# LED_driver_1_2.net
KiCad netlist of a schematic drawn in EAGLE
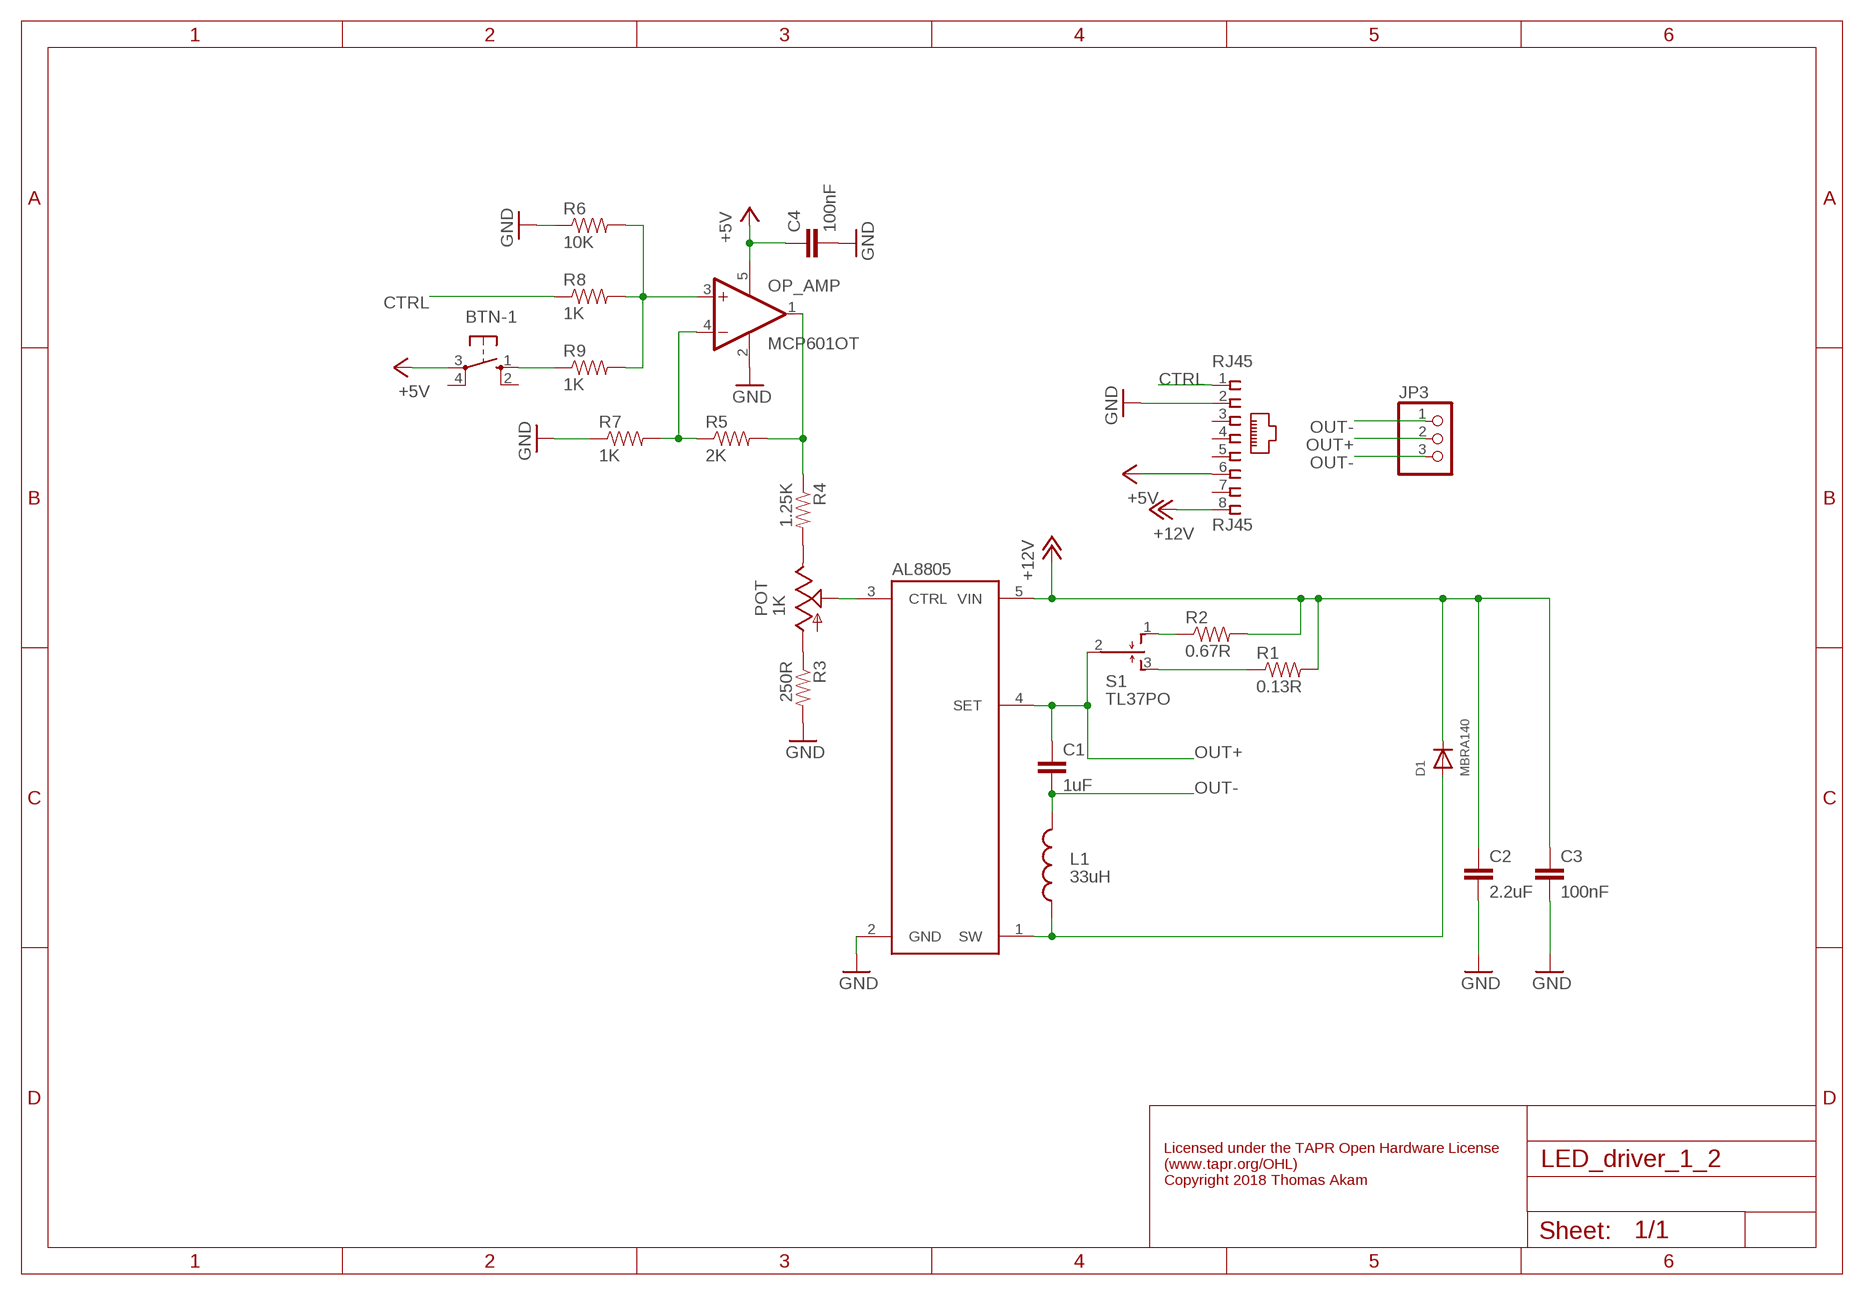
[diagram p0: schematic, sheet 1]

(export (version "E")
  (design (tool "Eeschema 10.0.6"))
  (components
    (comp (ref "AL8805")
      (value "AL8805")
      (footprint "eagle-import:SOT23-5")
      (libsource (lib "eagle-import") (part "AL8805"))
    )
    (comp (ref "BTN-1")
      (value "10-XX")
      (footprint "eagle-import:B3F-10XX")
      (fields (field (name "MPN") "B3F-1000"))
      (libsource (lib "eagle-import") (part "10-XX"))
    )
    (comp (ref "C1")
      (value "1uF")
      (footprint "eagle-import:C0805")
      (libsource (lib "eagle-import") (part "C-EUC0805"))
    )
    (comp (ref "C2")
      (value "2.2uF")
      (footprint "eagle-import:C0805")
      (libsource (lib "eagle-import") (part "C-EUC0805"))
    )
    (comp (ref "C3")
      (value "100nF")
      (footprint "eagle-import:C0805")
      (libsource (lib "eagle-import") (part "C-EUC0805"))
    )
    (comp (ref "C4")
      (value "100nF")
      (footprint "eagle-import:C0805")
      (libsource (lib "eagle-import") (part "C-EUC0805"))
    )
    (comp (ref "D1")
      (value "MBRA140")
      (footprint "eagle-import:SOD-123")
      (libsource (lib "eagle-import") (part "DIODESOD-123"))
    )
    (comp (ref "JP3")
      (value "PINHD-1X3")
      (footprint "eagle-import:1X03")
      (libsource (lib "eagle-import") (part "PINHD-1X3"))
    )
    (comp (ref "L1")
      (value "33uH")
      (footprint "eagle-import:SRN6045")
      (libsource (lib "eagle-import") (part "INDUCTORBOURNS_SRN6045"))
    )
    (comp (ref "OP_AMP")
      (value "MCP601OT")
      (footprint "eagle-import:SOT23-5")
      (libsource (lib "eagle-import") (part "MCP601OT"))
    )
    (comp (ref "POT")
      (value "1K")
      (footprint "eagle-import:RS3")
      (libsource (lib "eagle-import") (part "TRIM_US-RS3"))
    )
    (comp (ref "R1")
      (value "0.13R")
      (footprint "eagle-import:0805")
      (libsource (lib "eagle-import") (part "0.3OHM-1/8W-1%(0805)"))
    )
    (comp (ref "R2")
      (value "0.67R")
      (footprint "eagle-import:0805")
      (fields (field (name "PROD_ID") "RES-11622"))
      (libsource (lib "eagle-import") (part "0.3OHM-1/8W-1%(0805)"))
    )
    (comp (ref "R3")
      (value "250R")
      (footprint "eagle-import:0805")
      (fields (field (name "PROD_ID") "RES-11622"))
      (libsource (lib "eagle-import") (part "0.3OHM-1/8W-1%(0805)"))
    )
    (comp (ref "R4")
      (value "1.25K")
      (footprint "eagle-import:0805")
      (fields (field (name "PROD_ID") "RES-11622"))
      (libsource (lib "eagle-import") (part "0.3OHM-1/8W-1%(0805)"))
    )
    (comp (ref "R5")
      (value "2K")
      (footprint "eagle-import:0805")
      (fields (field (name "PROD_ID") "RES-11622"))
      (libsource (lib "eagle-import") (part "0.3OHM-1/8W-1%(0805)"))
    )
    (comp (ref "R6")
      (value "10K")
      (footprint "eagle-import:0805")
      (fields (field (name "PROD_ID") "RES-11622"))
      (libsource (lib "eagle-import") (part "0.3OHM-1/8W-1%(0805)"))
    )
    (comp (ref "R7")
      (value "1K")
      (footprint "eagle-import:0805")
      (fields (field (name "PROD_ID") "RES-11622"))
      (libsource (lib "eagle-import") (part "0.3OHM-1/8W-1%(0805)"))
    )
    (comp (ref "R8")
      (value "1K")
      (footprint "eagle-import:0805")
      (fields (field (name "PROD_ID") "RES-11622"))
      (libsource (lib "eagle-import") (part "0.3OHM-1/8W-1%(0805)"))
    )
    (comp (ref "R9")
      (value "1K")
      (footprint "eagle-import:0805")
      (fields (field (name "PROD_ID") "RES-11622"))
      (libsource (lib "eagle-import") (part "0.3OHM-1/8W-1%(0805)"))
    )
    (comp (ref "RJ45")
      (value "RJ45")
      (footprint "eagle-import:RJ45-NO-SHIELD-VERTICAL")
      (libsource (lib "eagle-import") (part "RJ45VERTICAL"))
    )
    (comp (ref "S1")
      (value "TL37PO")
      (footprint "eagle-import:TL3XPO")
      (libsource (lib "eagle-import") (part "TL37PO"))
    )
  )
  (nets
    (net (code "1") (name "+5V") (class "Default")
      (node (ref "BTN-1") (pin "3") (pinfunction "P_3") (pintype "passive"))
      (node (ref "C4") (pin "1") (pinfunction "1_1") (pintype "passive"))
      (node (ref "OP_AMP") (pin "5") (pinfunction "V+_5") (pintype "power_in"))
      (node (ref "RJ45") (pin "6") (pinfunction "6_6") (pintype "passive"))
    )
    (net (code "2") (name "+12V") (class "Default")
      (node (ref "AL8805") (pin "5") (pinfunction "VIN_5") (pintype "bidirectional"))
      (node (ref "C2") (pin "1") (pinfunction "1_1") (pintype "passive"))
      (node (ref "C3") (pin "1") (pinfunction "1_1") (pintype "passive"))
      (node (ref "D1") (pin "C") (pinfunction "C_C") (pintype "passive"))
      (node (ref "R1") (pin "2") (pinfunction "2_2") (pintype "passive"))
      (node (ref "R2") (pin "2") (pinfunction "2_2") (pintype "passive"))
      (node (ref "RJ45") (pin "8") (pinfunction "8_8") (pintype "passive"))
    )
    (net (code "3") (name "/CTRL") (class "Default")
      (node (ref "R8") (pin "1") (pinfunction "1_1") (pintype "passive"))
      (node (ref "RJ45") (pin "1") (pinfunction "1_1") (pintype "passive"))
    )
    (net (code "4") (name "/OUT+") (class "Default")
      (node (ref "AL8805") (pin "4") (pinfunction "SET_4") (pintype "bidirectional"))
      (node (ref "C1") (pin "1") (pinfunction "1_1") (pintype "passive"))
      (node (ref "JP3") (pin "2") (pinfunction "2_2") (pintype "passive"))
      (node (ref "S1") (pin "2") (pinfunction "P_2") (pintype "passive"))
    )
    (net (code "5") (name "/OUT-") (class "Default")
      (node (ref "C1") (pin "2") (pinfunction "2_2") (pintype "passive"))
      (node (ref "JP3") (pin "1") (pinfunction "1_1") (pintype "passive"))
      (node (ref "JP3") (pin "3") (pinfunction "3_3") (pintype "passive"))
      (node (ref "L1") (pin "2") (pinfunction "2_2") (pintype "passive"))
    )
    (net (code "6") (name "GND") (class "Default")
      (node (ref "AL8805") (pin "2") (pinfunction "GND_2") (pintype "bidirectional"))
      (node (ref "C2") (pin "2") (pinfunction "2_2") (pintype "passive"))
      (node (ref "C3") (pin "2") (pinfunction "2_2") (pintype "passive"))
      (node (ref "C4") (pin "2") (pinfunction "2_2") (pintype "passive"))
      (node (ref "OP_AMP") (pin "2") (pinfunction "V-_2") (pintype "power_in"))
      (node (ref "R3") (pin "2") (pinfunction "2_2") (pintype "passive"))
      (node (ref "R6") (pin "1") (pinfunction "1_1") (pintype "passive"))
      (node (ref "R7") (pin "1") (pinfunction "1_1") (pintype "passive"))
      (node (ref "RJ45") (pin "2") (pinfunction "2_2") (pintype "passive"))
    )
    (net (code "7") (name "Net-(AL8805-CTRL)") (class "Default")
      (node (ref "AL8805") (pin "3") (pinfunction "CTRL_3") (pintype "bidirectional"))
      (node (ref "POT") (pin "S") (pinfunction "S_S") (pintype "passive"))
    )
    (net (code "8") (name "Net-(AL8805-SW)") (class "Default")
      (node (ref "AL8805") (pin "1") (pinfunction "SW_1") (pintype "bidirectional"))
      (node (ref "D1") (pin "A") (pinfunction "A_A") (pintype "passive"))
      (node (ref "L1") (pin "1") (pinfunction "1_1") (pintype "passive"))
    )
    (net (code "9") (name "Net-(BTN-1-S)") (class "Default")
      (node (ref "BTN-1") (pin "1") (pinfunction "S_1") (pintype "passive"))
      (node (ref "R9") (pin "1") (pinfunction "1_1") (pintype "passive"))
    )
    (net (code "10") (name "Net-(OP_AMP-+IN)") (class "Default")
      (node (ref "OP_AMP") (pin "3") (pinfunction "+IN_3") (pintype "input"))
      (node (ref "R6") (pin "2") (pinfunction "2_2") (pintype "passive"))
      (node (ref "R8") (pin "2") (pinfunction "2_2") (pintype "passive"))
      (node (ref "R9") (pin "2") (pinfunction "2_2") (pintype "passive"))
    )
    (net (code "11") (name "Net-(OP_AMP--IN)") (class "Default")
      (node (ref "OP_AMP") (pin "4") (pinfunction "-IN_4") (pintype "input"))
      (node (ref "R5") (pin "1") (pinfunction "1_1") (pintype "passive"))
      (node (ref "R7") (pin "2") (pinfunction "2_2") (pintype "passive"))
    )
    (net (code "12") (name "Net-(OP_AMP-OUT)") (class "Default")
      (node (ref "OP_AMP") (pin "1") (pinfunction "OUT_1") (pintype "output"))
      (node (ref "R4") (pin "1") (pinfunction "1_1") (pintype "passive"))
      (node (ref "R5") (pin "2") (pinfunction "2_2") (pintype "passive"))
    )
    (net (code "13") (name "Net-(POT-PadA)") (class "Default")
      (node (ref "POT") (pin "A") (pinfunction "A_A") (pintype "passive"))
      (node (ref "R3") (pin "1") (pinfunction "1_1") (pintype "passive"))
    )
    (net (code "14") (name "Net-(POT-PadE)") (class "Default")
      (node (ref "POT") (pin "E") (pinfunction "E_E") (pintype "passive"))
      (node (ref "R4") (pin "2") (pinfunction "2_2") (pintype "passive"))
    )
    (net (code "15") (name "Net-(S1-O)") (class "Default")
      (node (ref "R2") (pin "1") (pinfunction "1_1") (pintype "passive"))
      (node (ref "S1") (pin "1") (pinfunction "O_1") (pintype "passive"))
    )
    (net (code "16") (name "Net-(S1-S)") (class "Default")
      (node (ref "R1") (pin "1") (pinfunction "1_1") (pintype "passive"))
      (node (ref "S1") (pin "3") (pinfunction "S_3") (pintype "passive"))
    )
    (net (code "17") (name "unconnected-(BTN-1-P1-Pad4)") (class "Default")
      (node (ref "BTN-1") (pin "4") (pinfunction "P1_4") (pintype "passive"))
    )
    (net (code "18") (name "unconnected-(BTN-1-S1-Pad2)") (class "Default")
      (node (ref "BTN-1") (pin "2") (pinfunction "S1_2") (pintype "passive"))
    )
    (net (code "19") (name "unconnected-(RJ45-Pad3)") (class "Default")
      (node (ref "RJ45") (pin "3") (pinfunction "3_3") (pintype "passive"))
    )
    (net (code "20") (name "unconnected-(RJ45-Pad4)") (class "Default")
      (node (ref "RJ45") (pin "4") (pinfunction "4_4") (pintype "passive"))
    )
    (net (code "21") (name "unconnected-(RJ45-Pad5)") (class "Default")
      (node (ref "RJ45") (pin "5") (pinfunction "5_5") (pintype "passive"))
    )
    (net (code "22") (name "unconnected-(RJ45-Pad7)") (class "Default")
      (node (ref "RJ45") (pin "7") (pinfunction "7_7") (pintype "passive"))
    )
  )
)
